# Omnimem.net
KiCad netlist of a schematic drawn in EAGLE
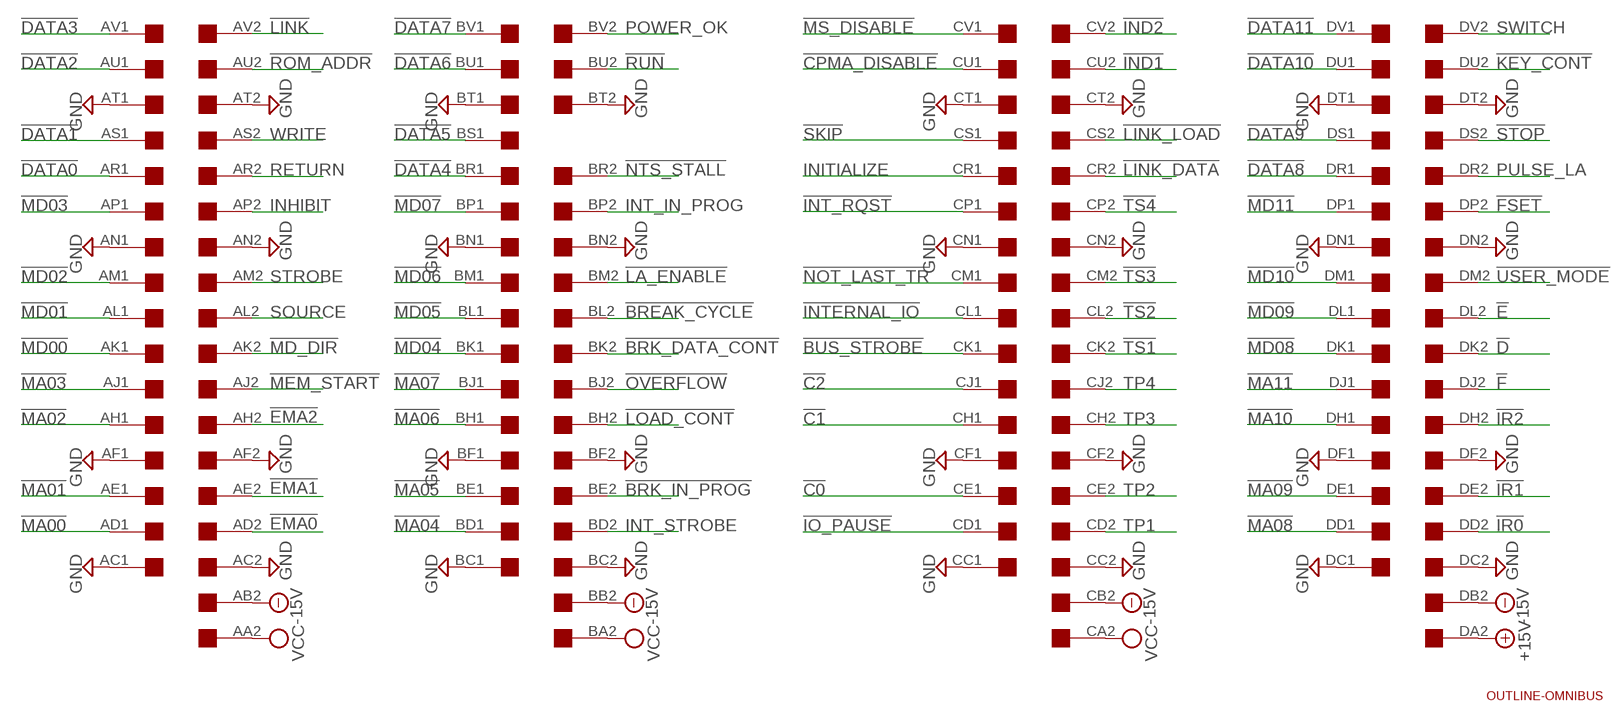
[diagram p0: schematic, sheet 1]
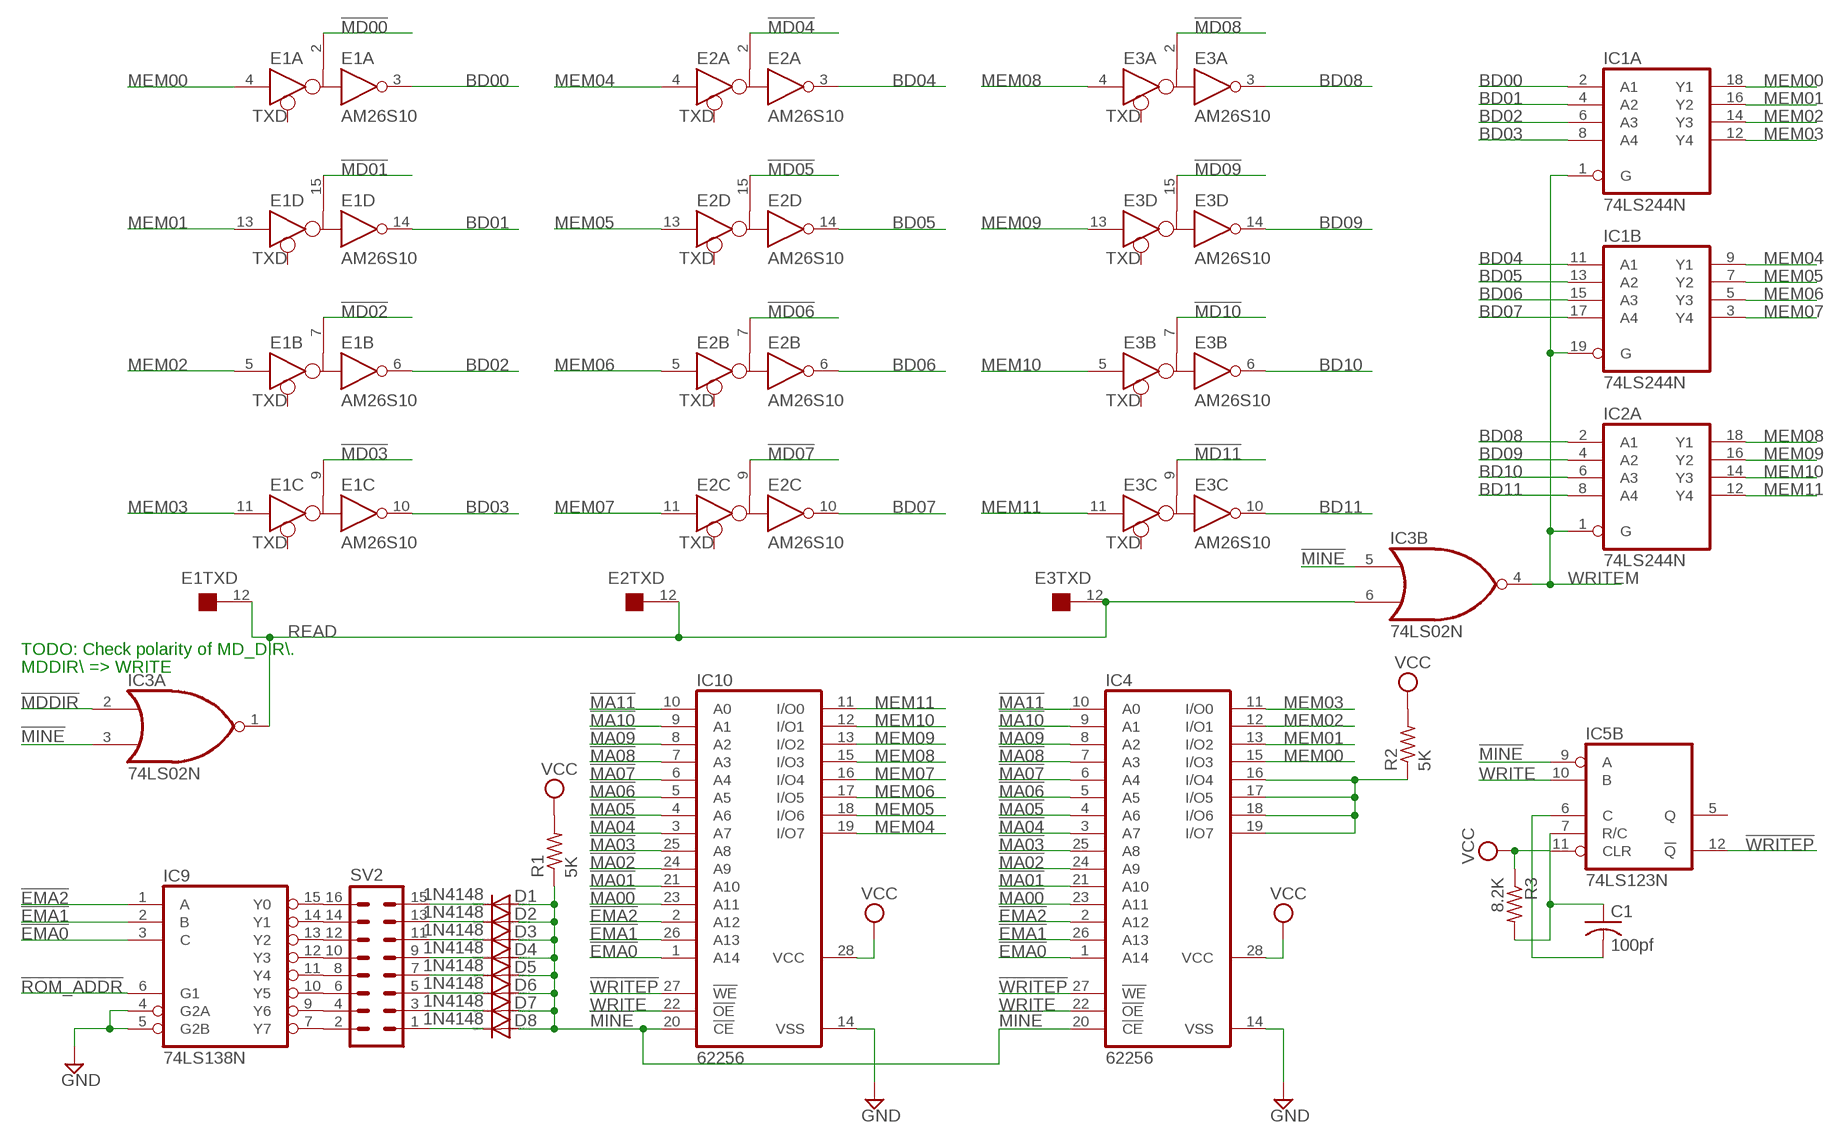
[diagram p1: schematic, sheet 2]
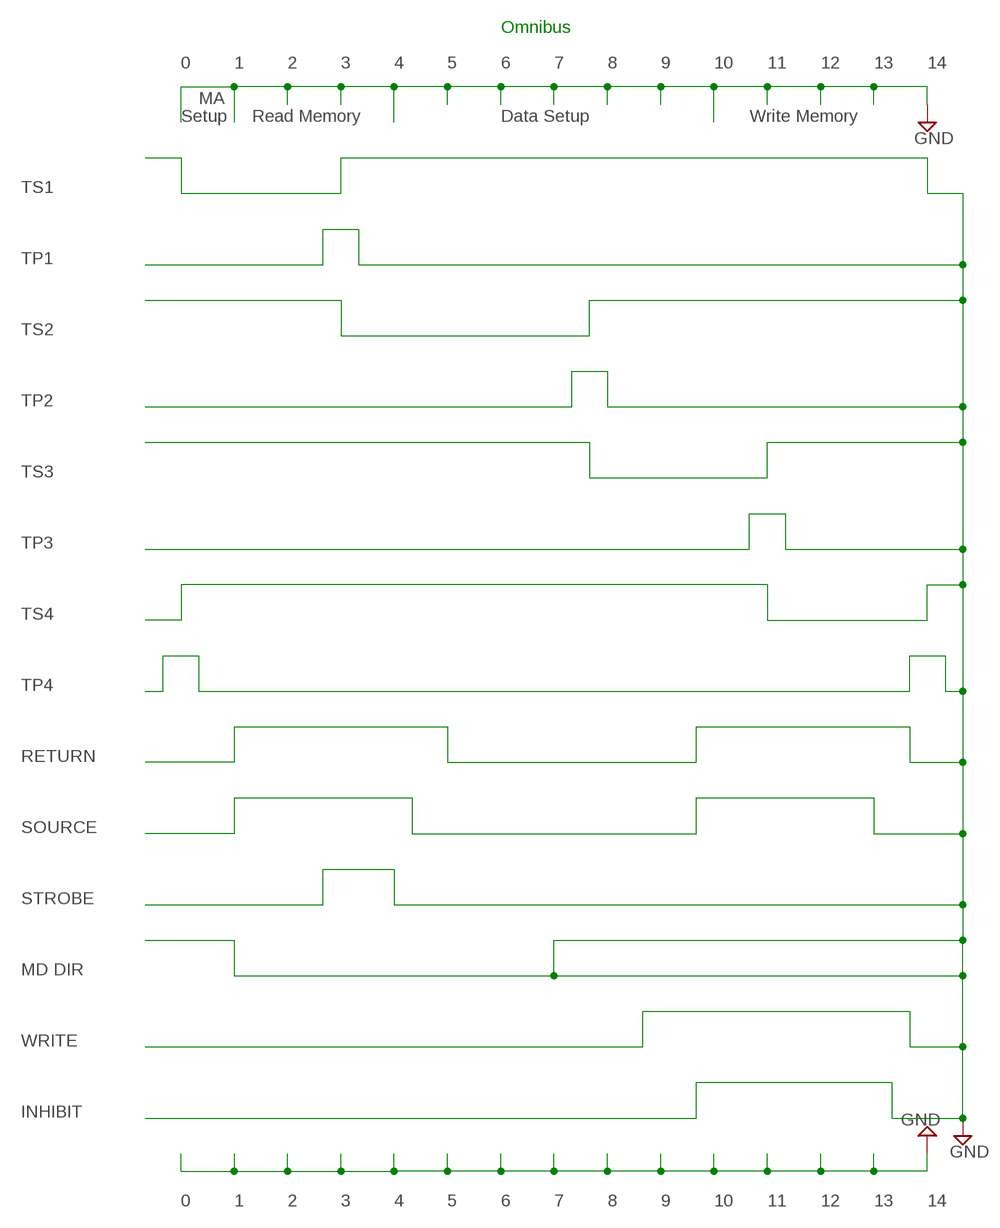
[diagram p2: schematic, sheet 3]

(export (version "E")
  (design (tool "Eeschema 10.0.6"))
  (components
    (comp (ref "C1")
      (value "100pf")
      (footprint "eagle-import:C050-025X075")
      (libsource (lib "eagle-import") (part "C-US050-025X075"))
    )
    (comp (ref "D1")
      (value "1N4148")
      (footprint "eagle-import:DO35-10")
      (libsource (lib "eagle-import") (part "1N4148DO35-10"))
    )
    (comp (ref "D2")
      (value "1N4148")
      (footprint "eagle-import:DO35-10")
      (libsource (lib "eagle-import") (part "1N4148DO35-10"))
    )
    (comp (ref "D3")
      (value "1N4148")
      (footprint "eagle-import:DO35-10")
      (libsource (lib "eagle-import") (part "1N4148DO35-10"))
    )
    (comp (ref "D4")
      (value "1N4148")
      (footprint "eagle-import:DO35-10")
      (libsource (lib "eagle-import") (part "1N4148DO35-10"))
    )
    (comp (ref "D5")
      (value "1N4148")
      (footprint "eagle-import:DO35-10")
      (libsource (lib "eagle-import") (part "1N4148DO35-10"))
    )
    (comp (ref "D6")
      (value "1N4148")
      (footprint "eagle-import:DO35-10")
      (libsource (lib "eagle-import") (part "1N4148DO35-10"))
    )
    (comp (ref "D7")
      (value "1N4148")
      (footprint "eagle-import:DO35-10")
      (libsource (lib "eagle-import") (part "1N4148DO35-10"))
    )
    (comp (ref "D8")
      (value "1N4148")
      (footprint "eagle-import:DO35-10")
      (libsource (lib "eagle-import") (part "1N4148DO35-10"))
    )
    (comp (ref "E1")
      (value "AM26S10")
      (footprint "eagle-import:DIL16")
      (libsource (lib "eagle-import") (part "AM26S10"))
    )
    (comp (ref "E2")
      (value "AM26S10")
      (footprint "eagle-import:DIL16")
      (libsource (lib "eagle-import") (part "AM26S10"))
    )
    (comp (ref "E3")
      (value "AM26S10")
      (footprint "eagle-import:DIL16")
      (libsource (lib "eagle-import") (part "AM26S10"))
    )
    (comp (ref "IC1")
      (value "74LS244N")
      (footprint "eagle-import:DIL20")
      (libsource (lib "eagle-import") (part "74244NLS"))
    )
    (comp (ref "IC2")
      (value "74LS244N")
      (footprint "eagle-import:DIL20")
      (libsource (lib "eagle-import") (part "74244NLS"))
    )
    (comp (ref "IC3")
      (value "74LS02N")
      (footprint "eagle-import:DIL14")
      (libsource (lib "eagle-import") (part "7402NLS"))
    )
    (comp (ref "IC4")
      (value "62256")
      (footprint "eagle-import:DIL28-6")
      (fields (field (name "MPN") "HN58C256AP85E"))
      (libsource (lib "eagle-import") (part "58C256P"))
    )
    (comp (ref "IC5")
      (value "74LS123N")
      (footprint "eagle-import:DIL16")
      (libsource (lib "eagle-import") (part "74123NLS"))
    )
    (comp (ref "IC9")
      (value "74LS138N")
      (footprint "eagle-import:DIL16")
      (libsource (lib "eagle-import") (part "74138NLS"))
    )
    (comp (ref "IC10")
      (value "62256")
      (footprint "eagle-import:DIL28-6")
      (fields (field (name "MPN") "HN58C256AP85E"))
      (libsource (lib "eagle-import") (part "58C256P"))
    )
    (comp (ref "R1")
      (value "5K")
      (footprint "eagle-import:0207_10")
      (libsource (lib "eagle-import") (part "R-US_0207/10"))
    )
    (comp (ref "R2")
      (value "5K")
      (footprint "eagle-import:0207_10")
      (libsource (lib "eagle-import") (part "R-US_0207/10"))
    )
    (comp (ref "R3")
      (value "8.2K")
      (footprint "eagle-import:0207_10")
      (libsource (lib "eagle-import") (part "R-US_0207/10"))
    )
    (comp (ref "SV2")
      (value "MA08-2")
      (footprint "eagle-import:MA08-2")
      (libsource (lib "eagle-import") (part "MA08-2"))
    )
    (comp (ref "U$1")
      (value "OUTLINE-OMNIBUS")
      (footprint "eagle-import:OMNIBUS")
      (libsource (lib "eagle-import") (part "OUTLINE-OMNIBUS"))
    )
    (comp (ref "U$2")
      (value "QUAD")
      (footprint "eagle-import:EDGE-CON8")
      (libsource (lib "eagle-import") (part "QUAD"))
    )
  )
  (nets
    (net (code "1") (name "+15V") (class "Default")
      (node (ref "U$2") (pin "DA2") (pinfunction "1_DA2") (pintype "bidirectional"))
    )
    (net (code "2") (name "-15V") (class "Default")
      (node (ref "U$2") (pin "AB2") (pinfunction "1_AB2") (pintype "bidirectional"))
      (node (ref "U$2") (pin "BB2") (pinfunction "1_BB2") (pintype "bidirectional"))
      (node (ref "U$2") (pin "CB2") (pinfunction "1_CB2") (pintype "bidirectional"))
      (node (ref "U$2") (pin "DB2") (pinfunction "1_DB2") (pintype "bidirectional"))
    )
    (net (code "3") (name "BD00") (class "Default")
      (node (ref "E1") (pin "3") (pinfunction "R_3") (pintype "output"))
      (node (ref "IC1") (pin "2") (pinfunction "A1_2") (pintype "input"))
    )
    (net (code "4") (name "BD01") (class "Default")
      (node (ref "E1") (pin "14") (pinfunction "R_14") (pintype "output"))
      (node (ref "IC1") (pin "4") (pinfunction "A2_4") (pintype "input"))
    )
    (net (code "5") (name "BD02") (class "Default")
      (node (ref "E1") (pin "6") (pinfunction "R_6") (pintype "output"))
      (node (ref "IC1") (pin "6") (pinfunction "A3_6") (pintype "input"))
    )
    (net (code "6") (name "BD03") (class "Default")
      (node (ref "E1") (pin "10") (pinfunction "R_10") (pintype "output"))
      (node (ref "IC1") (pin "8") (pinfunction "A4_8") (pintype "input"))
    )
    (net (code "7") (name "BD04") (class "Default")
      (node (ref "E2") (pin "3") (pinfunction "R_3") (pintype "output"))
      (node (ref "IC1") (pin "11") (pinfunction "A1_11") (pintype "input"))
    )
    (net (code "8") (name "BD05") (class "Default")
      (node (ref "E2") (pin "14") (pinfunction "R_14") (pintype "output"))
      (node (ref "IC1") (pin "13") (pinfunction "A2_13") (pintype "input"))
    )
    (net (code "9") (name "BD06") (class "Default")
      (node (ref "E2") (pin "6") (pinfunction "R_6") (pintype "output"))
      (node (ref "IC1") (pin "15") (pinfunction "A3_15") (pintype "input"))
    )
    (net (code "10") (name "BD07") (class "Default")
      (node (ref "E2") (pin "10") (pinfunction "R_10") (pintype "output"))
      (node (ref "IC1") (pin "17") (pinfunction "A4_17") (pintype "input"))
    )
    (net (code "11") (name "BD08") (class "Default")
      (node (ref "E3") (pin "3") (pinfunction "R_3") (pintype "output"))
      (node (ref "IC2") (pin "2") (pinfunction "A1_2") (pintype "input"))
    )
    (net (code "12") (name "BD09") (class "Default")
      (node (ref "E3") (pin "14") (pinfunction "R_14") (pintype "output"))
      (node (ref "IC2") (pin "4") (pinfunction "A2_4") (pintype "input"))
    )
    (net (code "13") (name "BD10") (class "Default")
      (node (ref "E3") (pin "6") (pinfunction "R_6") (pintype "output"))
      (node (ref "IC2") (pin "6") (pinfunction "A3_6") (pintype "input"))
    )
    (net (code "14") (name "BD11") (class "Default")
      (node (ref "E3") (pin "10") (pinfunction "R_10") (pintype "output"))
      (node (ref "IC2") (pin "8") (pinfunction "A4_8") (pintype "input"))
    )
    (net (code "15") (name "GND") (class "Default")
      (node (ref "IC10") (pin "14") (pinfunction "VSS_14") (pintype "power_in"))
      (node (ref "IC4") (pin "14") (pinfunction "VSS_14") (pintype "power_in"))
      (node (ref "IC9") (pin "4") (pinfunction "G2A_4") (pintype "input"))
      (node (ref "IC9") (pin "5") (pinfunction "G2B_5") (pintype "input"))
      (node (ref "U$2") (pin "AC1") (pinfunction "1_AC1") (pintype "bidirectional"))
      (node (ref "U$2") (pin "AC2") (pinfunction "1_AC2") (pintype "bidirectional"))
      (node (ref "U$2") (pin "AF1") (pinfunction "1_AF1") (pintype "bidirectional"))
      (node (ref "U$2") (pin "AF2") (pinfunction "1_AF2") (pintype "bidirectional"))
      (node (ref "U$2") (pin "AN1") (pinfunction "1_AN1") (pintype "bidirectional"))
      (node (ref "U$2") (pin "AN2") (pinfunction "1_AN2") (pintype "bidirectional"))
      (node (ref "U$2") (pin "AT1") (pinfunction "1_AT1") (pintype "bidirectional"))
      (node (ref "U$2") (pin "AT2") (pinfunction "1_AT2") (pintype "bidirectional"))
      (node (ref "U$2") (pin "BC1") (pinfunction "1_BC1") (pintype "bidirectional"))
      (node (ref "U$2") (pin "BC2") (pinfunction "1_BC2") (pintype "bidirectional"))
      (node (ref "U$2") (pin "BF1") (pinfunction "1_BF1") (pintype "bidirectional"))
      (node (ref "U$2") (pin "BF2") (pinfunction "1_BF2") (pintype "bidirectional"))
      (node (ref "U$2") (pin "BN1") (pinfunction "1_BN1") (pintype "bidirectional"))
      (node (ref "U$2") (pin "BN2") (pinfunction "1_BN2") (pintype "bidirectional"))
      (node (ref "U$2") (pin "BT1") (pinfunction "1_BT1") (pintype "bidirectional"))
      (node (ref "U$2") (pin "BT2") (pinfunction "1_BT2") (pintype "bidirectional"))
      (node (ref "U$2") (pin "CC1") (pinfunction "1_CC1") (pintype "bidirectional"))
      (node (ref "U$2") (pin "CC2") (pinfunction "1_CC2") (pintype "bidirectional"))
      (node (ref "U$2") (pin "CF1") (pinfunction "1_CF1") (pintype "bidirectional"))
      (node (ref "U$2") (pin "CF2") (pinfunction "1_CF2") (pintype "bidirectional"))
      (node (ref "U$2") (pin "CN1") (pinfunction "1_CN1") (pintype "bidirectional"))
      (node (ref "U$2") (pin "CN2") (pinfunction "1_CN2") (pintype "bidirectional"))
      (node (ref "U$2") (pin "CT1") (pinfunction "1_CT1") (pintype "bidirectional"))
      (node (ref "U$2") (pin "CT2") (pinfunction "1_CT2") (pintype "bidirectional"))
      (node (ref "U$2") (pin "DC1") (pinfunction "1_DC1") (pintype "bidirectional"))
      (node (ref "U$2") (pin "DC2") (pinfunction "1_DC2") (pintype "bidirectional"))
      (node (ref "U$2") (pin "DF1") (pinfunction "1_DF1") (pintype "bidirectional"))
      (node (ref "U$2") (pin "DF2") (pinfunction "1_DF2") (pintype "bidirectional"))
      (node (ref "U$2") (pin "DN1") (pinfunction "1_DN1") (pintype "bidirectional"))
      (node (ref "U$2") (pin "DN2") (pinfunction "1_DN2") (pintype "bidirectional"))
      (node (ref "U$2") (pin "DT1") (pinfunction "1_DT1") (pintype "bidirectional"))
      (node (ref "U$2") (pin "DT2") (pinfunction "1_DT2") (pintype "bidirectional"))
    )
    (net (code "16") (name "INHIBIT") (class "Default")
      (node (ref "U$2") (pin "AP2") (pinfunction "1_AP2") (pintype "bidirectional"))
    )
    (net (code "17") (name "INITIALIZE") (class "Default")
      (node (ref "U$2") (pin "CR1") (pinfunction "1_CR1") (pintype "bidirectional"))
    )
    (net (code "18") (name "INT_IN_PROG") (class "Default")
      (node (ref "U$2") (pin "BP2") (pinfunction "1_BP2") (pintype "bidirectional"))
    )
    (net (code "19") (name "INT_STROBE") (class "Default")
      (node (ref "U$2") (pin "BD2") (pinfunction "1_BD2") (pintype "bidirectional"))
    )
    (net (code "20") (name "MEM00") (class "Default")
      (node (ref "E1") (pin "4") (pinfunction "D_4") (pintype "input"))
      (node (ref "IC1") (pin "18") (pinfunction "Y1_18") (pintype "tri_state"))
      (node (ref "IC4") (pin "15") (pinfunction "I/O3_15") (pintype "tri_state"))
    )
    (net (code "21") (name "MEM01") (class "Default")
      (node (ref "E1") (pin "13") (pinfunction "D_13") (pintype "input"))
      (node (ref "IC1") (pin "16") (pinfunction "Y2_16") (pintype "tri_state"))
      (node (ref "IC4") (pin "13") (pinfunction "I/O2_13") (pintype "tri_state"))
    )
    (net (code "22") (name "MEM02") (class "Default")
      (node (ref "E1") (pin "5") (pinfunction "D_5") (pintype "input"))
      (node (ref "IC1") (pin "14") (pinfunction "Y3_14") (pintype "tri_state"))
      (node (ref "IC4") (pin "12") (pinfunction "I/O1_12") (pintype "tri_state"))
    )
    (net (code "23") (name "MEM03") (class "Default")
      (node (ref "E1") (pin "11") (pinfunction "D_11") (pintype "input"))
      (node (ref "IC1") (pin "12") (pinfunction "Y4_12") (pintype "tri_state"))
      (node (ref "IC4") (pin "11") (pinfunction "I/O0_11") (pintype "tri_state"))
    )
    (net (code "24") (name "MEM04") (class "Default")
      (node (ref "E2") (pin "4") (pinfunction "D_4") (pintype "input"))
      (node (ref "IC1") (pin "9") (pinfunction "Y1_9") (pintype "tri_state"))
      (node (ref "IC10") (pin "19") (pinfunction "I/O7_19") (pintype "tri_state"))
    )
    (net (code "25") (name "MEM05") (class "Default")
      (node (ref "E2") (pin "13") (pinfunction "D_13") (pintype "input"))
      (node (ref "IC1") (pin "7") (pinfunction "Y2_7") (pintype "tri_state"))
      (node (ref "IC10") (pin "18") (pinfunction "I/O6_18") (pintype "tri_state"))
    )
    (net (code "26") (name "MEM06") (class "Default")
      (node (ref "E2") (pin "5") (pinfunction "D_5") (pintype "input"))
      (node (ref "IC1") (pin "5") (pinfunction "Y3_5") (pintype "tri_state"))
      (node (ref "IC10") (pin "17") (pinfunction "I/O5_17") (pintype "tri_state"))
    )
    (net (code "27") (name "MEM07") (class "Default")
      (node (ref "E2") (pin "11") (pinfunction "D_11") (pintype "input"))
      (node (ref "IC1") (pin "3") (pinfunction "Y4_3") (pintype "tri_state"))
      (node (ref "IC10") (pin "16") (pinfunction "I/O4_16") (pintype "tri_state"))
    )
    (net (code "28") (name "MEM08") (class "Default")
      (node (ref "E3") (pin "4") (pinfunction "D_4") (pintype "input"))
      (node (ref "IC10") (pin "15") (pinfunction "I/O3_15") (pintype "tri_state"))
      (node (ref "IC2") (pin "18") (pinfunction "Y1_18") (pintype "tri_state"))
    )
    (net (code "29") (name "MEM09") (class "Default")
      (node (ref "E3") (pin "13") (pinfunction "D_13") (pintype "input"))
      (node (ref "IC10") (pin "13") (pinfunction "I/O2_13") (pintype "tri_state"))
      (node (ref "IC2") (pin "16") (pinfunction "Y2_16") (pintype "tri_state"))
    )
    (net (code "30") (name "MEM10") (class "Default")
      (node (ref "E3") (pin "5") (pinfunction "D_5") (pintype "input"))
      (node (ref "IC10") (pin "12") (pinfunction "I/O1_12") (pintype "tri_state"))
      (node (ref "IC2") (pin "14") (pinfunction "Y3_14") (pintype "tri_state"))
    )
    (net (code "31") (name "MEM11") (class "Default")
      (node (ref "E3") (pin "11") (pinfunction "D_11") (pintype "input"))
      (node (ref "IC10") (pin "11") (pinfunction "I/O0_11") (pintype "tri_state"))
      (node (ref "IC2") (pin "12") (pinfunction "Y4_12") (pintype "tri_state"))
    )
    (net (code "32") (name "Net-(D1-PadC)") (class "Default")
      (node (ref "D1") (pin "C") (pinfunction "C_C") (pintype "passive"))
      (node (ref "SV2") (pin "15") (pinfunction "15_15") (pintype "passive"))
    )
    (net (code "33") (name "Net-(D2-PadC)") (class "Default")
      (node (ref "D2") (pin "C") (pinfunction "C_C") (pintype "passive"))
      (node (ref "SV2") (pin "13") (pinfunction "13_13") (pintype "passive"))
    )
    (net (code "34") (name "Net-(D3-PadC)") (class "Default")
      (node (ref "D3") (pin "C") (pinfunction "C_C") (pintype "passive"))
      (node (ref "SV2") (pin "11") (pinfunction "11_11") (pintype "passive"))
    )
    (net (code "35") (name "Net-(D4-PadC)") (class "Default")
      (node (ref "D4") (pin "C") (pinfunction "C_C") (pintype "passive"))
      (node (ref "SV2") (pin "9") (pinfunction "9_9") (pintype "passive"))
    )
    (net (code "36") (name "Net-(D5-PadC)") (class "Default")
      (node (ref "D5") (pin "C") (pinfunction "C_C") (pintype "passive"))
      (node (ref "SV2") (pin "7") (pinfunction "7_7") (pintype "passive"))
    )
    (net (code "37") (name "Net-(D6-PadC)") (class "Default")
      (node (ref "D6") (pin "C") (pinfunction "C_C") (pintype "passive"))
      (node (ref "SV2") (pin "5") (pinfunction "5_5") (pintype "passive"))
    )
    (net (code "38") (name "Net-(D7-PadC)") (class "Default")
      (node (ref "D7") (pin "C") (pinfunction "C_C") (pintype "passive"))
      (node (ref "SV2") (pin "3") (pinfunction "3_3") (pintype "passive"))
    )
    (net (code "39") (name "Net-(D8-PadC)") (class "Default")
      (node (ref "D8") (pin "C") (pinfunction "C_C") (pintype "passive"))
      (node (ref "SV2") (pin "1") (pinfunction "1_1") (pintype "passive"))
    )
    (net (code "40") (name "Net-(IC4-I{slash}O4)") (class "Default")
      (node (ref "IC4") (pin "16") (pinfunction "I/O4_16") (pintype "tri_state"))
      (node (ref "IC4") (pin "17") (pinfunction "I/O5_17") (pintype "tri_state"))
      (node (ref "IC4") (pin "18") (pinfunction "I/O6_18") (pintype "tri_state"))
      (node (ref "IC4") (pin "19") (pinfunction "I/O7_19") (pintype "tri_state"))
      (node (ref "R2") (pin "1") (pinfunction "1_1") (pintype "passive"))
    )
    (net (code "41") (name "Net-(IC5B-C)") (class "Default")
      (node (ref "C1") (pin "2") (pinfunction "2_2") (pintype "passive"))
      (node (ref "IC5") (pin "6") (pinfunction "C_6") (pintype "input"))
    )
    (net (code "42") (name "Net-(IC5B-R{slash}C)") (class "Default")
      (node (ref "C1") (pin "1") (pinfunction "1_1") (pintype "passive"))
      (node (ref "IC5") (pin "7") (pinfunction "R/C_7") (pintype "input"))
      (node (ref "R3") (pin "2") (pinfunction "2_2") (pintype "passive"))
    )
    (net (code "43") (name "Net-(IC9A-Y0)") (class "Default")
      (node (ref "IC9") (pin "15") (pinfunction "Y0_15") (pintype "output"))
      (node (ref "SV2") (pin "16") (pinfunction "16_16") (pintype "passive"))
    )
    (net (code "44") (name "Net-(IC9A-Y1)") (class "Default")
      (node (ref "IC9") (pin "14") (pinfunction "Y1_14") (pintype "output"))
      (node (ref "SV2") (pin "14") (pinfunction "14_14") (pintype "passive"))
    )
    (net (code "45") (name "Net-(IC9A-Y2)") (class "Default")
      (node (ref "IC9") (pin "13") (pinfunction "Y2_13") (pintype "output"))
      (node (ref "SV2") (pin "12") (pinfunction "12_12") (pintype "passive"))
    )
    (net (code "46") (name "Net-(IC9A-Y3)") (class "Default")
      (node (ref "IC9") (pin "12") (pinfunction "Y3_12") (pintype "output"))
      (node (ref "SV2") (pin "10") (pinfunction "10_10") (pintype "passive"))
    )
    (net (code "47") (name "Net-(IC9A-Y4)") (class "Default")
      (node (ref "IC9") (pin "11") (pinfunction "Y4_11") (pintype "output"))
      (node (ref "SV2") (pin "8") (pinfunction "8_8") (pintype "passive"))
    )
    (net (code "48") (name "Net-(IC9A-Y5)") (class "Default")
      (node (ref "IC9") (pin "10") (pinfunction "Y5_10") (pintype "output"))
      (node (ref "SV2") (pin "6") (pinfunction "6_6") (pintype "passive"))
    )
    (net (code "49") (name "Net-(IC9A-Y6)") (class "Default")
      (node (ref "IC9") (pin "9") (pinfunction "Y6_9") (pintype "output"))
      (node (ref "SV2") (pin "4") (pinfunction "4_4") (pintype "passive"))
    )
    (net (code "50") (name "Net-(IC9A-Y7)") (class "Default")
      (node (ref "IC9") (pin "7") (pinfunction "Y7_7") (pintype "output"))
      (node (ref "SV2") (pin "2") (pinfunction "2_2") (pintype "passive"))
    )
    (net (code "51") (name "POWER_OK") (class "Default")
      (node (ref "U$2") (pin "BV2") (pinfunction "1_BV2") (pintype "bidirectional"))
    )
    (net (code "52") (name "PULSE_LA") (class "Default")
      (node (ref "U$2") (pin "DR2") (pinfunction "1_DR2") (pintype "bidirectional"))
    )
    (net (code "53") (name "READ") (class "Default")
      (node (ref "E1") (pin "12") (pinfunction "TXD_12") (pintype "input"))
      (node (ref "E2") (pin "12") (pinfunction "TXD_12") (pintype "input"))
      (node (ref "E3") (pin "12") (pinfunction "TXD_12") (pintype "input"))
      (node (ref "IC3") (pin "1") (pinfunction "O_1") (pintype "output"))
      (node (ref "IC3") (pin "6") (pinfunction "I1_6") (pintype "input"))
    )
    (net (code "54") (name "RETURN") (class "Default")
      (node (ref "U$2") (pin "AR2") (pinfunction "1_AR2") (pintype "bidirectional"))
    )
    (net (code "55") (name "SOURCE") (class "Default")
      (node (ref "U$2") (pin "AL2") (pinfunction "1_AL2") (pintype "bidirectional"))
    )
    (net (code "56") (name "STROBE") (class "Default")
      (node (ref "U$2") (pin "AM2") (pinfunction "1_AM2") (pintype "bidirectional"))
    )
    (net (code "57") (name "SWITCH") (class "Default")
      (node (ref "U$2") (pin "DV2") (pinfunction "1_DV2") (pintype "bidirectional"))
    )
    (net (code "58") (name "TP1") (class "Default")
      (node (ref "U$2") (pin "CD2") (pinfunction "1_CD2") (pintype "bidirectional"))
    )
    (net (code "59") (name "TP2") (class "Default")
      (node (ref "U$2") (pin "CE2") (pinfunction "1_CE2") (pintype "bidirectional"))
    )
    (net (code "60") (name "TP3") (class "Default")
      (node (ref "U$2") (pin "CH2") (pinfunction "1_CH2") (pintype "bidirectional"))
    )
    (net (code "61") (name "TP4") (class "Default")
      (node (ref "U$2") (pin "CJ2") (pinfunction "1_CJ2") (pintype "bidirectional"))
    )
    (net (code "62") (name "VCC") (class "Default")
      (node (ref "IC10") (pin "28") (pinfunction "VCC_28") (pintype "power_in"))
      (node (ref "IC4") (pin "28") (pinfunction "VCC_28") (pintype "power_in"))
      (node (ref "IC5") (pin "11") (pinfunction "CLR_11") (pintype "input"))
      (node (ref "R1") (pin "2") (pinfunction "2_2") (pintype "passive"))
      (node (ref "R2") (pin "2") (pinfunction "2_2") (pintype "passive"))
      (node (ref "R3") (pin "1") (pinfunction "1_1") (pintype "passive"))
      (node (ref "U$2") (pin "AA2") (pinfunction "1_AA2") (pintype "bidirectional"))
      (node (ref "U$2") (pin "BA2") (pinfunction "1_BA2") (pintype "bidirectional"))
      (node (ref "U$2") (pin "CA2") (pinfunction "1_CA2") (pintype "bidirectional"))
    )
    (net (code "63") (name "WRITE") (class "Default")
      (node (ref "IC10") (pin "22") (pinfunction "~{OE}_22") (pintype "input"))
      (node (ref "IC4") (pin "22") (pinfunction "~{OE}_22") (pintype "input"))
      (node (ref "IC5") (pin "10") (pinfunction "B_10") (pintype "input"))
      (node (ref "U$2") (pin "AS2") (pinfunction "1_AS2") (pintype "bidirectional"))
    )
    (net (code "64") (name "WRITEM") (class "Default")
      (node (ref "IC1") (pin "1") (pinfunction "G_1") (pintype "input"))
      (node (ref "IC1") (pin "19") (pinfunction "G_19") (pintype "input"))
      (node (ref "IC2") (pin "1") (pinfunction "G_1") (pintype "input"))
      (node (ref "IC3") (pin "4") (pinfunction "O_4") (pintype "output"))
    )
    (net (code "65") (name "unconnected-(IC5B-Q-Pad5)") (class "Default")
      (node (ref "IC5") (pin "5") (pinfunction "Q_5") (pintype "output"))
    )
    (net (code "66") (name "~{BREAK_CYCLE}") (class "Default")
      (node (ref "U$2") (pin "BL2") (pinfunction "1_BL2") (pintype "bidirectional"))
    )
    (net (code "67") (name "~{BRK_DATA_CONT}") (class "Default")
      (node (ref "U$2") (pin "BK2") (pinfunction "1_BK2") (pintype "bidirectional"))
    )
    (net (code "68") (name "~{BRK_IN_PROG}") (class "Default")
      (node (ref "U$2") (pin "BE2") (pinfunction "1_BE2") (pintype "bidirectional"))
    )
    (net (code "69") (name "~{BUS_STROBE}") (class "Default")
      (node (ref "U$2") (pin "CK1") (pinfunction "1_CK1") (pintype "bidirectional"))
    )
    (net (code "70") (name "~{C0}") (class "Default")
      (node (ref "U$2") (pin "CE1") (pinfunction "1_CE1") (pintype "bidirectional"))
    )
    (net (code "71") (name "~{C1}") (class "Default")
      (node (ref "U$2") (pin "CH1") (pinfunction "1_CH1") (pintype "bidirectional"))
    )
    (net (code "72") (name "~{C2}") (class "Default")
      (node (ref "U$2") (pin "CJ1") (pinfunction "1_CJ1") (pintype "bidirectional"))
    )
    (net (code "73") (name "~{CPMA_DISABLE}") (class "Default")
      (node (ref "U$2") (pin "CU1") (pinfunction "1_CU1") (pintype "bidirectional"))
    )
    (net (code "74") (name "~{DATA0}") (class "Default")
      (node (ref "U$2") (pin "AR1") (pinfunction "1_AR1") (pintype "bidirectional"))
    )
    (net (code "75") (name "~{DATA1}") (class "Default")
      (node (ref "U$2") (pin "AS1") (pinfunction "1_AS1") (pintype "bidirectional"))
    )
    (net (code "76") (name "~{DATA2}") (class "Default")
      (node (ref "U$2") (pin "AU1") (pinfunction "1_AU1") (pintype "bidirectional"))
    )
    (net (code "77") (name "~{DATA3}") (class "Default")
      (node (ref "U$2") (pin "AV1") (pinfunction "1_AV1") (pintype "bidirectional"))
    )
    (net (code "78") (name "~{DATA4}") (class "Default")
      (node (ref "U$2") (pin "BR1") (pinfunction "1_BR1") (pintype "bidirectional"))
    )
    (net (code "79") (name "~{DATA5}") (class "Default")
      (node (ref "U$2") (pin "BS1") (pinfunction "1_BS1") (pintype "bidirectional"))
    )
    (net (code "80") (name "~{DATA6}") (class "Default")
      (node (ref "U$2") (pin "BU1") (pinfunction "1_BU1") (pintype "bidirectional"))
    )
    (net (code "81") (name "~{DATA7}") (class "Default")
      (node (ref "U$2") (pin "BV1") (pinfunction "1_BV1") (pintype "bidirectional"))
    )
    (net (code "82") (name "~{DATA8}") (class "Default")
      (node (ref "U$2") (pin "DR1") (pinfunction "1_DR1") (pintype "bidirectional"))
    )
    (net (code "83") (name "~{DATA9}") (class "Default")
      (node (ref "U$2") (pin "DS1") (pinfunction "1_DS1") (pintype "bidirectional"))
    )
    (net (code "84") (name "~{DATA10}") (class "Default")
      (node (ref "U$2") (pin "DU1") (pinfunction "1_DU1") (pintype "bidirectional"))
    )
    (net (code "85") (name "~{DATA11}") (class "Default")
      (node (ref "U$2") (pin "DV1") (pinfunction "1_DV1") (pintype "bidirectional"))
    )
    (net (code "86") (name "~{D}") (class "Default")
      (node (ref "U$2") (pin "DK2") (pinfunction "1_DK2") (pintype "bidirectional"))
    )
    (net (code "87") (name "~{EMA0}") (class "Default")
      (node (ref "IC10") (pin "1") (pinfunction "A14_1") (pintype "input"))
      (node (ref "IC4") (pin "1") (pinfunction "A14_1") (pintype "input"))
      (node (ref "IC9") (pin "3") (pinfunction "C_3") (pintype "input"))
      (node (ref "U$2") (pin "AD2") (pinfunction "1_AD2") (pintype "bidirectional"))
    )
    (net (code "88") (name "~{EMA1}") (class "Default")
      (node (ref "IC10") (pin "26") (pinfunction "A13_26") (pintype "input"))
      (node (ref "IC4") (pin "26") (pinfunction "A13_26") (pintype "input"))
      (node (ref "IC9") (pin "2") (pinfunction "B_2") (pintype "input"))
      (node (ref "U$2") (pin "AE2") (pinfunction "1_AE2") (pintype "bidirectional"))
    )
    (net (code "89") (name "~{EMA2}") (class "Default")
      (node (ref "IC10") (pin "2") (pinfunction "A12_2") (pintype "input"))
      (node (ref "IC4") (pin "2") (pinfunction "A12_2") (pintype "input"))
      (node (ref "IC9") (pin "1") (pinfunction "A_1") (pintype "input"))
      (node (ref "U$2") (pin "AH2") (pinfunction "1_AH2") (pintype "bidirectional"))
    )
    (net (code "90") (name "~{E}") (class "Default")
      (node (ref "U$2") (pin "DL2") (pinfunction "1_DL2") (pintype "bidirectional"))
    )
    (net (code "91") (name "~{FSET}") (class "Default")
      (node (ref "U$2") (pin "DP2") (pinfunction "1_DP2") (pintype "bidirectional"))
    )
    (net (code "92") (name "~{F}") (class "Default")
      (node (ref "U$2") (pin "DJ2") (pinfunction "1_DJ2") (pintype "bidirectional"))
    )
    (net (code "93") (name "~{IND1}") (class "Default")
      (node (ref "U$2") (pin "CU2") (pinfunction "1_CU2") (pintype "bidirectional"))
    )
    (net (code "94") (name "~{IND2}") (class "Default")
      (node (ref "U$2") (pin "CV2") (pinfunction "1_CV2") (pintype "bidirectional"))
    )
    (net (code "95") (name "~{INTERNAL_IO}") (class "Default")
      (node (ref "U$2") (pin "CL1") (pinfunction "1_CL1") (pintype "bidirectional"))
    )
    (net (code "96") (name "~{INT_RQST}") (class "Default")
      (node (ref "U$2") (pin "CP1") (pinfunction "1_CP1") (pintype "bidirectional"))
    )
    (net (code "97") (name "~{IO_PAUSE}") (class "Default")
      (node (ref "U$2") (pin "CD1") (pinfunction "1_CD1") (pintype "bidirectional"))
    )
    (net (code "98") (name "~{IR0}") (class "Default")
      (node (ref "U$2") (pin "DD2") (pinfunction "1_DD2") (pintype "bidirectional"))
    )
    (net (code "99") (name "~{IR1}") (class "Default")
      (node (ref "U$2") (pin "DE2") (pinfunction "1_DE2") (pintype "bidirectional"))
    )
    (net (code "100") (name "~{IR2}") (class "Default")
      (node (ref "U$2") (pin "DH2") (pinfunction "1_DH2") (pintype "bidirectional"))
    )
    (net (code "101") (name "~{KEY_CONT}") (class "Default")
      (node (ref "U$2") (pin "DU2") (pinfunction "1_DU2") (pintype "bidirectional"))
    )
    (net (code "102") (name "~{LA_ENABLE}") (class "Default")
      (node (ref "U$2") (pin "BM2") (pinfunction "1_BM2") (pintype "bidirectional"))
    )
    (net (code "103") (name "~{LINK_DATA}") (class "Default")
      (node (ref "U$2") (pin "CR2") (pinfunction "1_CR2") (pintype "bidirectional"))
    )
    (net (code "104") (name "~{LINK_LOAD}") (class "Default")
      (node (ref "U$2") (pin "CS2") (pinfunction "1_CS2") (pintype "bidirectional"))
    )
    (net (code "105") (name "~{LINK}") (class "Default")
      (node (ref "U$2") (pin "AV2") (pinfunction "1_AV2") (pintype "bidirectional"))
    )
    (net (code "106") (name "~{LOAD_CONT}") (class "Default")
      (node (ref "U$2") (pin "BH2") (pinfunction "1_BH2") (pintype "bidirectional"))
    )
    (net (code "107") (name "~{MA00}") (class "Default")
      (node (ref "IC10") (pin "23") (pinfunction "A11_23") (pintype "input"))
      (node (ref "IC4") (pin "23") (pinfunction "A11_23") (pintype "input"))
      (node (ref "U$2") (pin "AD1") (pinfunction "1_AD1") (pintype "bidirectional"))
    )
    (net (code "108") (name "~{MA01}") (class "Default")
      (node (ref "IC10") (pin "21") (pinfunction "A10_21") (pintype "input"))
      (node (ref "IC4") (pin "21") (pinfunction "A10_21") (pintype "input"))
      (node (ref "U$2") (pin "AE1") (pinfunction "1_AE1") (pintype "bidirectional"))
    )
    (net (code "109") (name "~{MA02}") (class "Default")
      (node (ref "IC10") (pin "24") (pinfunction "A9_24") (pintype "input"))
      (node (ref "IC4") (pin "24") (pinfunction "A9_24") (pintype "input"))
      (node (ref "U$2") (pin "AH1") (pinfunction "1_AH1") (pintype "bidirectional"))
    )
    (net (code "110") (name "~{MA03}") (class "Default")
      (node (ref "IC10") (pin "25") (pinfunction "A8_25") (pintype "input"))
      (node (ref "IC4") (pin "25") (pinfunction "A8_25") (pintype "input"))
      (node (ref "U$2") (pin "AJ1") (pinfunction "1_AJ1") (pintype "bidirectional"))
    )
    (net (code "111") (name "~{MA04}") (class "Default")
      (node (ref "IC10") (pin "3") (pinfunction "A7_3") (pintype "input"))
      (node (ref "IC4") (pin "3") (pinfunction "A7_3") (pintype "input"))
      (node (ref "U$2") (pin "BD1") (pinfunction "1_BD1") (pintype "bidirectional"))
    )
    (net (code "112") (name "~{MA05}") (class "Default")
      (node (ref "IC10") (pin "4") (pinfunction "A6_4") (pintype "input"))
      (node (ref "IC4") (pin "4") (pinfunction "A6_4") (pintype "input"))
      (node (ref "U$2") (pin "BE1") (pinfunction "1_BE1") (pintype "bidirectional"))
    )
    (net (code "113") (name "~{MA06}") (class "Default")
      (node (ref "IC10") (pin "5") (pinfunction "A5_5") (pintype "input"))
      (node (ref "IC4") (pin "5") (pinfunction "A5_5") (pintype "input"))
      (node (ref "U$2") (pin "BH1") (pinfunction "1_BH1") (pintype "bidirectional"))
    )
    (net (code "114") (name "~{MA07}") (class "Default")
      (node (ref "IC10") (pin "6") (pinfunction "A4_6") (pintype "input"))
      (node (ref "IC4") (pin "6") (pinfunction "A4_6") (pintype "input"))
      (node (ref "U$2") (pin "BJ1") (pinfunction "1_BJ1") (pintype "bidirectional"))
    )
    (net (code "115") (name "~{MA08}") (class "Default")
      (node (ref "IC10") (pin "7") (pinfunction "A3_7") (pintype "input"))
      (node (ref "IC4") (pin "7") (pinfunction "A3_7") (pintype "input"))
      (node (ref "U$2") (pin "DD1") (pinfunction "1_DD1") (pintype "bidirectional"))
    )
    (net (code "116") (name "~{MA09}") (class "Default")
      (node (ref "IC10") (pin "8") (pinfunction "A2_8") (pintype "input"))
      (node (ref "IC4") (pin "8") (pinfunction "A2_8") (pintype "input"))
      (node (ref "U$2") (pin "DE1") (pinfunction "1_DE1") (pintype "bidirectional"))
    )
    (net (code "117") (name "~{MA10}") (class "Default")
      (node (ref "IC10") (pin "9") (pinfunction "A1_9") (pintype "input"))
      (node (ref "IC4") (pin "9") (pinfunction "A1_9") (pintype "input"))
      (node (ref "U$2") (pin "DH1") (pinfunction "1_DH1") (pintype "bidirectional"))
    )
    (net (code "118") (name "~{MA11}") (class "Default")
      (node (ref "IC10") (pin "10") (pinfunction "A0_10") (pintype "input"))
      (node (ref "IC4") (pin "10") (pinfunction "A0_10") (pintype "input"))
      (node (ref "U$2") (pin "DJ1") (pinfunction "1_DJ1") (pintype "bidirectional"))
    )
    (net (code "119") (name "~{MD00}") (class "Default")
      (node (ref "E1") (pin "2") (pinfunction "B_2") (pintype "bidirectional"))
      (node (ref "U$2") (pin "AK1") (pinfunction "1_AK1") (pintype "bidirectional"))
    )
    (net (code "120") (name "~{MD01}") (class "Default")
      (node (ref "E1") (pin "15") (pinfunction "B_15") (pintype "bidirectional"))
      (node (ref "U$2") (pin "AL1") (pinfunction "1_AL1") (pintype "bidirectional"))
    )
    (net (code "121") (name "~{MD02}") (class "Default")
      (node (ref "E1") (pin "7") (pinfunction "B_7") (pintype "bidirectional"))
      (node (ref "U$2") (pin "AM1") (pinfunction "1_AM1") (pintype "bidirectional"))
    )
    (net (code "122") (name "~{MD03}") (class "Default")
      (node (ref "E1") (pin "9") (pinfunction "B_9") (pintype "bidirectional"))
      (node (ref "U$2") (pin "AP1") (pinfunction "1_AP1") (pintype "bidirectional"))
    )
    (net (code "123") (name "~{MD04}") (class "Default")
      (node (ref "E2") (pin "2") (pinfunction "B_2") (pintype "bidirectional"))
      (node (ref "U$2") (pin "BK1") (pinfunction "1_BK1") (pintype "bidirectional"))
    )
    (net (code "124") (name "~{MD05}") (class "Default")
      (node (ref "E2") (pin "15") (pinfunction "B_15") (pintype "bidirectional"))
      (node (ref "U$2") (pin "BL1") (pinfunction "1_BL1") (pintype "bidirectional"))
    )
    (net (code "125") (name "~{MD06}") (class "Default")
      (node (ref "E2") (pin "7") (pinfunction "B_7") (pintype "bidirectional"))
      (node (ref "U$2") (pin "BM1") (pinfunction "1_BM1") (pintype "bidirectional"))
    )
    (net (code "126") (name "~{MD07}") (class "Default")
      (node (ref "E2") (pin "9") (pinfunction "B_9") (pintype "bidirectional"))
      (node (ref "U$2") (pin "BP1") (pinfunction "1_BP1") (pintype "bidirectional"))
    )
    (net (code "127") (name "~{MD08}") (class "Default")
      (node (ref "E3") (pin "2") (pinfunction "B_2") (pintype "bidirectional"))
      (node (ref "U$2") (pin "DK1") (pinfunction "1_DK1") (pintype "bidirectional"))
    )
    (net (code "128") (name "~{MD09}") (class "Default")
      (node (ref "E3") (pin "15") (pinfunction "B_15") (pintype "bidirectional"))
      (node (ref "U$2") (pin "DL1") (pinfunction "1_DL1") (pintype "bidirectional"))
    )
    (net (code "129") (name "~{MD10}") (class "Default")
      (node (ref "E3") (pin "7") (pinfunction "B_7") (pintype "bidirectional"))
      (node (ref "U$2") (pin "DM1") (pinfunction "1_DM1") (pintype "bidirectional"))
    )
    (net (code "130") (name "~{MD11}") (class "Default")
      (node (ref "E3") (pin "9") (pinfunction "B_9") (pintype "bidirectional"))
      (node (ref "U$2") (pin "DP1") (pinfunction "1_DP1") (pintype "bidirectional"))
    )
    (net (code "131") (name "~{MDDIR}") (class "Default")
      (node (ref "IC3") (pin "2") (pinfunction "I0_2") (pintype "input"))
    )
    (net (code "132") (name "~{MD_DIR}") (class "Default")
      (node (ref "U$2") (pin "AK2") (pinfunction "1_AK2") (pintype "bidirectional"))
    )
    (net (code "133") (name "~{MEM_START}") (class "Default")
      (node (ref "U$2") (pin "AJ2") (pinfunction "1_AJ2") (pintype "bidirectional"))
    )
    (net (code "134") (name "~{MINE}") (class "Default")
      (node (ref "D1") (pin "A") (pinfunction "A_A") (pintype "passive"))
      (node (ref "D2") (pin "A") (pinfunction "A_A") (pintype "passive"))
      (node (ref "D3") (pin "A") (pinfunction "A_A") (pintype "passive"))
      (node (ref "D4") (pin "A") (pinfunction "A_A") (pintype "passive"))
      (node (ref "D5") (pin "A") (pinfunction "A_A") (pintype "passive"))
      (node (ref "D6") (pin "A") (pinfunction "A_A") (pintype "passive"))
      (node (ref "D7") (pin "A") (pinfunction "A_A") (pintype "passive"))
      (node (ref "D8") (pin "A") (pinfunction "A_A") (pintype "passive"))
      (node (ref "IC10") (pin "20") (pinfunction "~{CE}_20") (pintype "input"))
      (node (ref "IC3") (pin "3") (pinfunction "I1_3") (pintype "input"))
      (node (ref "IC3") (pin "5") (pinfunction "I0_5") (pintype "input"))
      (node (ref "IC4") (pin "20") (pinfunction "~{CE}_20") (pintype "input"))
      (node (ref "IC5") (pin "9") (pinfunction "A_9") (pintype "input"))
      (node (ref "R1") (pin "1") (pinfunction "1_1") (pintype "passive"))
    )
    (net (code "135") (name "~{MS_DISABLE}") (class "Default")
      (node (ref "U$2") (pin "CV1") (pinfunction "1_CV1") (pintype "bidirectional"))
    )
    (net (code "136") (name "~{NOT_LAST_TR}") (class "Default")
      (node (ref "U$2") (pin "CM1") (pinfunction "1_CM1") (pintype "bidirectional"))
    )
    (net (code "137") (name "~{NTS_STALL}") (class "Default")
      (node (ref "U$2") (pin "BR2") (pinfunction "1_BR2") (pintype "bidirectional"))
    )
    (net (code "138") (name "~{OVERFLOW}") (class "Default")
      (node (ref "U$2") (pin "BJ2") (pinfunction "1_BJ2") (pintype "bidirectional"))
    )
    (net (code "139") (name "~{ROM_ADDR}") (class "Default")
      (node (ref "IC9") (pin "6") (pinfunction "G1_6") (pintype "input"))
      (node (ref "U$2") (pin "AU2") (pinfunction "1_AU2") (pintype "bidirectional"))
    )
    (net (code "140") (name "~{RUN}") (class "Default")
      (node (ref "U$2") (pin "BU2") (pinfunction "1_BU2") (pintype "bidirectional"))
    )
    (net (code "141") (name "~{SKIP}") (class "Default")
      (node (ref "U$2") (pin "CS1") (pinfunction "1_CS1") (pintype "bidirectional"))
    )
    (net (code "142") (name "~{STOP}") (class "Default")
      (node (ref "U$2") (pin "DS2") (pinfunction "1_DS2") (pintype "bidirectional"))
    )
    (net (code "143") (name "~{TS1}") (class "Default")
      (node (ref "U$2") (pin "CK2") (pinfunction "1_CK2") (pintype "bidirectional"))
    )
    (net (code "144") (name "~{TS2}") (class "Default")
      (node (ref "U$2") (pin "CL2") (pinfunction "1_CL2") (pintype "bidirectional"))
    )
    (net (code "145") (name "~{TS3}") (class "Default")
      (node (ref "U$2") (pin "CM2") (pinfunction "1_CM2") (pintype "bidirectional"))
    )
    (net (code "146") (name "~{TS4}") (class "Default")
      (node (ref "U$2") (pin "CP2") (pinfunction "1_CP2") (pintype "bidirectional"))
    )
    (net (code "147") (name "~{USER_MODE}") (class "Default")
      (node (ref "U$2") (pin "DM2") (pinfunction "1_DM2") (pintype "bidirectional"))
    )
    (net (code "148") (name "~{WRITEP}") (class "Default")
      (node (ref "IC10") (pin "27") (pinfunction "~{WE}_27") (pintype "input"))
      (node (ref "IC4") (pin "27") (pinfunction "~{WE}_27") (pintype "input"))
      (node (ref "IC5") (pin "12") (pinfunction "~{Q}_12") (pintype "output"))
    )
  )
)
